# Buttonboard.net
KiCad netlist of a schematic drawn in Altium Designer
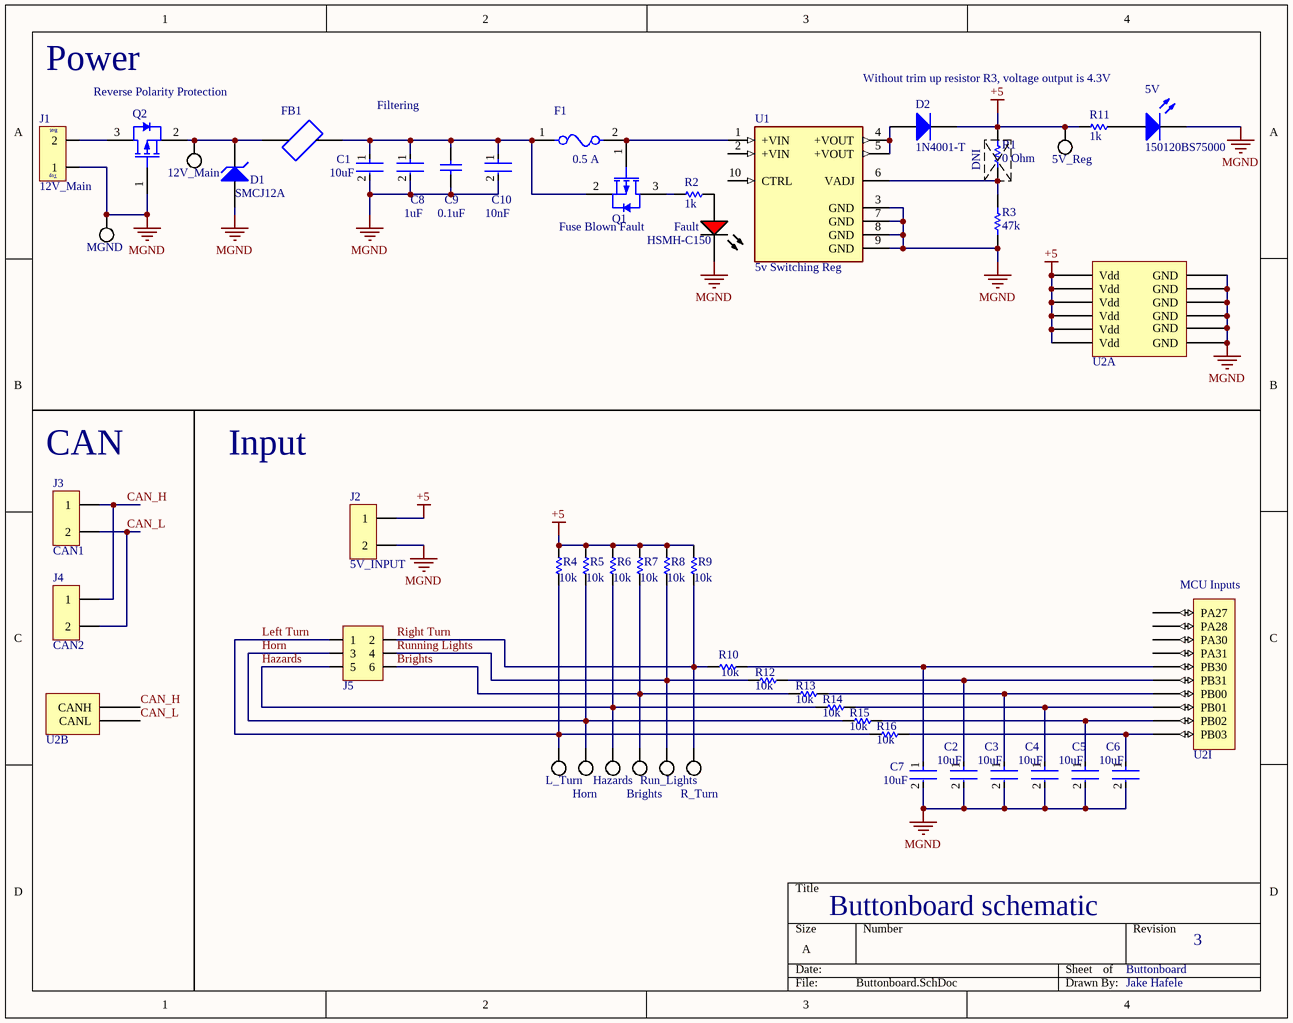
[diagram p0: Buttonboard.SchDoc]

(export (version "E")
  (design (tool "Eeschema 10.0.6"))
  (components
    (comp (ref "5V")
      (value "150120BS75000")
      (footprint "1206_A")
      (description "SMD mono-color Chip LED, WL-SMCW, Blue")
      (fields (field (name "MANUFACTURER") "Wuerth Elektronik"))
      (libsource (lib "Altium Content Vault") (part "WE-LED_K1A2-2"))
    )
    (comp (ref "5V_Reg")
      (value "EPAD")
      (footprint "EPAD")
      (description "Pad for probing signals")
      (libsource (lib "PrISUm-Discrete") (part "EPAD"))
    )
    (comp (ref "12V_Main")
      (value "EPAD")
      (footprint "EPAD")
      (description "Pad for probing signals")
      (libsource (lib "PrISUm-Discrete") (part "EPAD"))
    )
    (comp (ref "Brights")
      (value "EPAD")
      (footprint "EPAD")
      (description "Pad for probing signals")
      (libsource (lib "PrISUm-Discrete") (part "EPAD"))
    )
    (comp (ref "C1")
      (value "CL31A106MOHNNNE")
      (footprint "FP-CL31-IPC_A")
      (description "Cap Ceramic 10uF 16V X5R ±20% SMD 1206 +85°C Embossed T/R")
      (fields (field (name "CAPACITANCE") "10uF") (field (name "TOLERANCE") "20%"))
      (libsource (lib "Altium Content Vault") (part "b4654b650e69147ec39a6b967a45e02"))
    )
    (comp (ref "C2")
      (value "CL31A106MOHNNNE")
      (footprint "FP-CL31-IPC_A")
      (description "Cap Ceramic 10uF 16V X5R ±20% SMD 1206 +85°C Embossed T/R")
      (fields (field (name "CAPACITANCE") "10uF") (field (name "TOLERANCE") "20%"))
      (libsource (lib "Altium Content Vault") (part "b4654b650e69147ec39a6b967a45e02"))
    )
    (comp (ref "C3")
      (value "CL31A106MOHNNNE")
      (footprint "FP-CL31-IPC_A")
      (description "Cap Ceramic 10uF 16V X5R ±20% SMD 1206 +85°C Embossed T/R")
      (fields (field (name "CAPACITANCE") "10uF") (field (name "TOLERANCE") "20%"))
      (libsource (lib "Altium Content Vault") (part "b4654b650e69147ec39a6b967a45e02"))
    )
    (comp (ref "C4")
      (value "CL31A106MOHNNNE")
      (footprint "FP-CL31-IPC_A")
      (description "Cap Ceramic 10uF 16V X5R ±20% SMD 1206 +85°C Embossed T/R")
      (fields (field (name "CAPACITANCE") "10uF") (field (name "TOLERANCE") "20%"))
      (libsource (lib "Altium Content Vault") (part "b4654b650e69147ec39a6b967a45e02"))
    )
    (comp (ref "C5")
      (value "CL31A106MOHNNNE")
      (footprint "FP-CL31-IPC_A")
      (description "Cap Ceramic 10uF 16V X5R ±20% SMD 1206 +85°C Embossed T/R")
      (fields (field (name "CAPACITANCE") "10uF") (field (name "TOLERANCE") "20%"))
      (libsource (lib "Altium Content Vault") (part "b4654b650e69147ec39a6b967a45e02"))
    )
    (comp (ref "C6")
      (value "CL31A106MOHNNNE")
      (footprint "FP-CL31-IPC_A")
      (description "Cap Ceramic 10uF 16V X5R ±20% SMD 1206 +85°C Embossed T/R")
      (fields (field (name "CAPACITANCE") "10uF") (field (name "TOLERANCE") "20%"))
      (libsource (lib "Altium Content Vault") (part "b4654b650e69147ec39a6b967a45e02"))
    )
    (comp (ref "C7")
      (value "CL31A106MOHNNNE")
      (footprint "FP-CL31-IPC_A")
      (description "Cap Ceramic 10uF 16V X5R ±20% SMD 1206 +85°C Embossed T/R")
      (fields (field (name "CAPACITANCE") "10uF") (field (name "TOLERANCE") "20%"))
      (libsource (lib "Altium Content Vault") (part "b4654b650e69147ec39a6b967a45e02"))
    )
    (comp (ref "C8")
      (value "CL31F105ZOCNNNC")
      (footprint "FP-CL31-IPC_A")
      (description "Cap Ceramic 1uF 16V Y5V -20/+80% SMD 1206 +85°C Embossed T/R")
      (fields (field (name "TOLERANCE") "80%") (field (name "CAPACITANCE") "1uF"))
      (libsource (lib "Altium Content Vault") (part "b4654b650e69147ec39a6b967a45e02"))
    )
    (comp (ref "C9")
      (value "08055C104JAT2A")
      (footprint "CAPC2013X94X50LL20T25")
      (description "Chip Capacitor, 0.1 uF, +/- 5%, 50 V, -55 to 125 degC, 0805 (2012 Metric), RoHS, Tape and Reel")
      (fields
        (field (name "CAPACITANCE") "0.1uF")
        (field (name "TOLERANCE") "5%")
        (field (name "MANUFACTURER") "AVX")
      )
      (libsource (lib "Altium Content Vault") (part "CAP-NP-2"))
    )
    (comp (ref "C10")
      (value "CGA3E2X8R2A103K080AD")
      (footprint "FP-CGA3E-0_3-0_1-IPC_A")
      (description "Cap Ceramic 10nF 100V X8R 10% Pad SMD 0603 +150°C Automotive T/R")
      (fields (field (name "CAPACITANCE") "10nF") (field (name "TOLERANCE") "10%"))
      (libsource (lib "Altium Content Vault") (part "b4654b650e69147ec39a6b967a45e02"))
    )
    (comp (ref "D1")
      (value "SMCJ12A")
      (footprint "LFUS-DO-214AB-2_V")
      (fields (field (name "MANUFACTURER") "Littelfuse"))
      (libsource (lib "Altium Content Vault") (part "DZEN-AK-2"))
    )
    (comp (ref "D2")
      (value "1N4001-T")
      (footprint "DIOD-DO-41-P-2_V")
      (description "1.0 A Rectifier, 15 pF, 50 V, -65 to 150 degC, 2-Pin DO-41 Plastic, RoHS, Tape and Reel")
      (fields (field (name "MANUFACTURER") "Diodes Inc"))
      (libsource (lib "Altium Content Vault") (part "DIOD-D-A1K2-2"))
    )
    (comp (ref "DNI") (value "DO NOT INSTALL") (libsource (lib "PrISUm-Discrete") (part "DNI")))
    (comp (ref "F1")
      (value "0.5 A")
      (footprint "FP-0155-MFG")
      (description "FUSE BLOK CARTRIDGE 125V 10A SMD")
      (fields
        (field (name "MANUFACTURER") "Littelfuse Inc")
        (field (name "OCTOPART") "https://octopart.com/01550900m-littelfuse-9291575")
      )
      (libsource (lib "Altium Content Vault") (part "5bcf9b9f640e542cf0359d10258e979"))
    )
    (comp (ref "Fault")
      (value "HSMH-C150")
      (footprint "AVAG-HSMX-C150_V")
      (description "LED Uni-Color Red, 65 mW, 25 mA, -40 to 85 degC, 2-Pin SMD, RoHS, Tape and Reel")
      (fields (field (name "MANUFACTURER") "Avago"))
      (libsource (lib "Altium Content Vault") (part "LED-RED-AK-2"))
    )
    (comp (ref "FB1")
      (value "HI1206N800R-10")
      (footprint "FB_HI1206N800R-10")
      (description "80 Ohms @ 100MHz 1 Power, Signal Line Ferrite Bead 1206 (3216 Metric) 3A 35mOhm")
      (fields
        (field (name "MF") "Laird-Signal Integrity")
        (field (name "DIGI-KEY_PART_NUMBER") "240-2409-1-ND")
      )
      (libsource (lib "HI1206N800R-10") (part "HI1206N800R-10"))
    )
    (comp (ref "Hazards")
      (value "EPAD")
      (footprint "EPAD")
      (description "Pad for probing signals")
      (libsource (lib "PrISUm-Discrete") (part "EPAD"))
    )
    (comp (ref "Horn")
      (value "EPAD")
      (footprint "EPAD")
      (description "Pad for probing signals")
      (libsource (lib "PrISUm-Discrete") (part "EPAD"))
    )
    (comp (ref "J1")
      (value "12V_Main")
      (footprint "CONN_2P_MEGAFIT_HORIZONTAL")
      (fields
        (field (name "MANUFACTURER PART NUMBER") "0768250002")
        (field (name "MANUFACTURER") "Molex")
        (field (name "DIGIKEY PART NUMBER") "WM11969-ND")
      )
      (libsource (lib "Connectors") (part "CONN_2P_MEGAFIT_HORIZONTAL"))
    )
    (comp (ref "J2")
      (value "5V_INPUT")
      (footprint "Mini-Fit Jr. 2")
      (description "Mini-Fit Jr. 2-pin Right Angle")
      (fields
        (field (name "MANUFACTURER") "Molex Inc")
        (field (name "MANUFACTURER PART NUMBER") "0039300020")
      )
      (libsource (lib "PrISUm-Connectors") (part "Mini-Fit Jr. 2-pin"))
    )
    (comp (ref "J3")
      (value "CAN1")
      (footprint "Mini-Fit Jr. 2")
      (description "Mini-Fit Jr. 2-pin Right Angle")
      (fields
        (field (name "MANUFACTURER") "Molex Inc")
        (field (name "MANUFACTURER PART NUMBER") "0039300020")
      )
      (libsource (lib "PrISUm-Connectors") (part "Mini-Fit Jr. 2-pin"))
    )
    (comp (ref "J4")
      (value "CAN2")
      (footprint "Mini-Fit Jr. 2")
      (description "Mini-Fit Jr. 2-pin Right Angle")
      (fields
        (field (name "MANUFACTURER") "Molex Inc")
        (field (name "MANUFACTURER PART NUMBER") "0039300020")
      )
      (libsource (lib "PrISUm-Connectors") (part "Mini-Fit Jr. 2-pin"))
    )
    (comp (ref "J5")
      (value "Molex Mini-Fit Jr. 6-Pin")
      (footprint "Molex Mini-Fit Jr. 6-Pin")
      (description "6-Pin Molex Mini-Fit Jr. Header  through hole")
      (fields (field (name "MANUFACTURER") "Molex") (field (name "DRAWN BY") "Aaron Mills"))
      (libsource (lib "PrISUm-Connectors") (part "Molex Mini-Fit Jr. 6-Pin"))
    )
    (comp (ref "L_Turn")
      (value "EPAD")
      (footprint "EPAD")
      (description "Pad for probing signals")
      (libsource (lib "PrISUm-Discrete") (part "EPAD"))
    )
    (comp (ref "MGND")
      (value "EPAD")
      (footprint "EPAD")
      (description "Pad for probing signals")
      (libsource (lib "PrISUm-Discrete") (part "EPAD"))
    )
    (comp (ref "Q1")
      (value "Fuse Blown Fault")
      (footprint "INTR-SOT-23-3_V")
      (fields (field (name "MANUFACTURER") "International Rectifier"))
      (libsource (lib "Altium Content Vault") (part "PEMOS-GSD-3"))
    )
    (comp (ref "Q2")
      (value "Reverse Polarity Protection")
      (footprint "INTR-SOT-23-3_V")
      (fields (field (name "MANUFACTURER") "International Rectifier"))
      (libsource (lib "Altium Content Vault") (part "PEMOS-GSD-3"))
    )
    (comp (ref "R1")
      (value "0 Ohm")
      (footprint "RESC2013X50X30LL20T20")
      (fields (field (name "PART NUMBER") "CRCW080533K0JNEA") (field (name "MANUFACTURER") "Vishay Dale"))
      (libsource (lib "Altium Content Vault") (part "RES"))
    )
    (comp (ref "R2")
      (value "1k")
      (footprint "0805_B")
      (fields (field (name "Comment") "Resistor"))
      (libsource (lib "Resistors") (part "Resistor"))
    )
    (comp (ref "R3")
      (value "47k")
      (footprint "RESC2013X60X35ML10T20")
      (fields (field (name "MANUFACTURER") "Yageo") (field (name "PART NUMBER") "RC0805FR-078K66L"))
      (libsource (lib "Altium Content Vault") (part "RES"))
    )
    (comp (ref "R4")
      (value "10k")
      (footprint "0805_B")
      (description "0805 10kOhm resistor 1% 1/8W")
      (fields (field (name "Comment") "1% 1/8W"))
      (libsource (lib "Resistors") (part "MCR10EZHF1002"))
    )
    (comp (ref "R5")
      (value "10k")
      (footprint "0805_B")
      (description "0805 10kOhm resistor 1% 1/8W")
      (fields (field (name "Comment") "1% 1/8W"))
      (libsource (lib "Resistors") (part "MCR10EZHF1002"))
    )
    (comp (ref "R6")
      (value "10k")
      (footprint "0805_B")
      (description "0805 10kOhm resistor 1% 1/8W")
      (fields (field (name "Comment") "1% 1/8W"))
      (libsource (lib "Resistors") (part "MCR10EZHF1002"))
    )
    (comp (ref "R7")
      (value "10k")
      (footprint "0805_B")
      (description "0805 10kOhm resistor 1% 1/8W")
      (fields (field (name "Comment") "1% 1/8W"))
      (libsource (lib "Resistors") (part "MCR10EZHF1002"))
    )
    (comp (ref "R8")
      (value "10k")
      (footprint "0805_B")
      (description "0805 10kOhm resistor 1% 1/8W")
      (fields (field (name "Comment") "1% 1/8W"))
      (libsource (lib "Resistors") (part "MCR10EZHF1002"))
    )
    (comp (ref "R9")
      (value "10k")
      (footprint "0805_B")
      (description "0805 10kOhm resistor 1% 1/8W")
      (fields (field (name "Comment") "1% 1/8W"))
      (libsource (lib "Resistors") (part "MCR10EZHF1002"))
    )
    (comp (ref "R10")
      (value "10k")
      (footprint "0805_B")
      (description "0805 10kOhm resistor 1% 1/8W")
      (fields (field (name "Comment") "1% 1/8W"))
      (libsource (lib "Resistors") (part "MCR10EZHF1002"))
    )
    (comp (ref "R11")
      (value "1k")
      (footprint "0805_B")
      (fields (field (name "Comment") "Resistor"))
      (libsource (lib "Resistors") (part "Resistor"))
    )
    (comp (ref "R12")
      (value "10k")
      (footprint "0805_B")
      (description "0805 10kOhm resistor 1% 1/8W")
      (fields (field (name "Comment") "1% 1/8W"))
      (libsource (lib "Resistors") (part "MCR10EZHF1002"))
    )
    (comp (ref "R13")
      (value "10k")
      (footprint "0805_B")
      (description "0805 10kOhm resistor 1% 1/8W")
      (fields (field (name "Comment") "1% 1/8W"))
      (libsource (lib "Resistors") (part "MCR10EZHF1002"))
    )
    (comp (ref "R14")
      (value "10k")
      (footprint "0805_B")
      (description "0805 10kOhm resistor 1% 1/8W")
      (fields (field (name "Comment") "1% 1/8W"))
      (libsource (lib "Resistors") (part "MCR10EZHF1002"))
    )
    (comp (ref "R15")
      (value "10k")
      (footprint "0805_B")
      (description "0805 10kOhm resistor 1% 1/8W")
      (fields (field (name "Comment") "1% 1/8W"))
      (libsource (lib "Resistors") (part "MCR10EZHF1002"))
    )
    (comp (ref "R16")
      (value "10k")
      (footprint "0805_B")
      (description "0805 10kOhm resistor 1% 1/8W")
      (fields (field (name "Comment") "1% 1/8W"))
      (libsource (lib "Resistors") (part "MCR10EZHF1002"))
    )
    (comp (ref "Run_Lights")
      (value "EPAD")
      (footprint "EPAD")
      (description "Pad for probing signals")
      (libsource (lib "PrISUm-Discrete") (part "EPAD"))
    )
    (comp (ref "R_Turn")
      (value "EPAD")
      (footprint "EPAD")
      (description "Pad for probing signals")
      (libsource (lib "PrISUm-Discrete") (part "EPAD"))
    )
    (comp (ref "U1")
      (value "5v Switching Reg")
      (footprint "5v Reg")
      (description "1A DC/DC-Converter 'INNOLINE' SMD reg")
      (fields (field (name "MF") "Recom Power") (field (name "MP") "R-78AA5.0-1.0SMD-R"))
      (libsource (lib "PrISUm-ICs") (part "5v Switching Reg"))
    )
    (comp (ref "U2")
      (value "S+")
      (footprint "Compute S+")
      (description "Need to get 4 of PPPC161LFBN-RC")
      (libsource (lib "PrISUm-ICs") (part "S+"))
    )
  )
  (nets
    (net (code "1") (name "+5") (class "Default")
      (node (ref "5V_Reg") (pin "1") (pinfunction "1_1") (pintype "passive"))
      (node (ref "D2") (pin "2") (pinfunction "K_2") (pintype "passive"))
      (node (ref "J2") (pin "1") (pinfunction "1_1") (pintype "passive"))
      (node (ref "R1") (pin "2") (pinfunction "2_2") (pintype "passive"))
      (node (ref "R11") (pin "2") (pinfunction "2_2") (pintype "passive"))
      (node (ref "R4") (pin "2") (pinfunction "2_2") (pintype "passive"))
      (node (ref "R5") (pin "2") (pinfunction "2_2") (pintype "passive"))
      (node (ref "R6") (pin "2") (pinfunction "2_2") (pintype "passive"))
      (node (ref "R7") (pin "2") (pinfunction "2_2") (pintype "passive"))
      (node (ref "R8") (pin "2") (pinfunction "2_2") (pintype "passive"))
      (node (ref "R9") (pin "2") (pinfunction "2_2") (pintype "passive"))
      (node (ref "U2") (pin "Vdd") (pinfunction "Vdd_Vdd") (pintype "passive"))
    )
    (net (code "2") (name "/Brights") (class "Default")
      (node (ref "Brights") (pin "1") (pinfunction "1_1") (pintype "passive"))
      (node (ref "J5") (pin "6") (pinfunction "6_6") (pintype "passive"))
      (node (ref "R13") (pin "2") (pinfunction "2_2") (pintype "passive"))
      (node (ref "R7") (pin "1") (pinfunction "1_1") (pintype "passive"))
    )
    (net (code "3") (name "/CAN_H") (class "Default")
      (node (ref "J3") (pin "1") (pinfunction "1_1") (pintype "passive"))
      (node (ref "J4") (pin "1") (pinfunction "1_1") (pintype "passive"))
      (node (ref "U2") (pin "CANH") (pinfunction "CANH_CANH") (pintype "passive"))
    )
    (net (code "4") (name "/CAN_L") (class "Default")
      (node (ref "J3") (pin "2") (pinfunction "2_2") (pintype "passive"))
      (node (ref "J4") (pin "2") (pinfunction "2_2") (pintype "passive"))
      (node (ref "U2") (pin "CANL") (pinfunction "CANL_CANL") (pintype "passive"))
    )
    (net (code "5") (name "/Hazards") (class "Default")
      (node (ref "Hazards") (pin "1") (pinfunction "1_1") (pintype "passive"))
      (node (ref "J5") (pin "5") (pinfunction "5_5") (pintype "passive"))
      (node (ref "R14") (pin "2") (pinfunction "2_2") (pintype "passive"))
      (node (ref "R6") (pin "1") (pinfunction "1_1") (pintype "passive"))
    )
    (net (code "6") (name "/Horn") (class "Default")
      (node (ref "Horn") (pin "1") (pinfunction "1_1") (pintype "passive"))
      (node (ref "J5") (pin "3") (pinfunction "3_3") (pintype "passive"))
      (node (ref "R15") (pin "2") (pinfunction "2_2") (pintype "passive"))
      (node (ref "R5") (pin "1") (pinfunction "1_1") (pintype "passive"))
    )
    (net (code "7") (name "/Left Turn") (class "Default")
      (node (ref "J5") (pin "1") (pinfunction "1_1") (pintype "passive"))
      (node (ref "L_Turn") (pin "1") (pinfunction "1_1") (pintype "passive"))
      (node (ref "R16") (pin "2") (pinfunction "2_2") (pintype "passive"))
      (node (ref "R4") (pin "1") (pinfunction "1_1") (pintype "passive"))
    )
    (net (code "8") (name "/Right Turn") (class "Default")
      (node (ref "J5") (pin "2") (pinfunction "2_2") (pintype "passive"))
      (node (ref "R10") (pin "2") (pinfunction "2_2") (pintype "passive"))
      (node (ref "R9") (pin "1") (pinfunction "1_1") (pintype "passive"))
      (node (ref "R_Turn") (pin "1") (pinfunction "1_1") (pintype "passive"))
    )
    (net (code "9") (name "/Running Lights") (class "Default")
      (node (ref "J5") (pin "4") (pinfunction "4_4") (pintype "passive"))
      (node (ref "R12") (pin "2") (pinfunction "2_2") (pintype "passive"))
      (node (ref "R8") (pin "1") (pinfunction "1_1") (pintype "passive"))
      (node (ref "Run_Lights") (pin "1") (pinfunction "1_1") (pintype "passive"))
    )
    (net (code "10") (name "MGND") (class "Default")
      (node (ref "5V") (pin "1") (pinfunction "K_1") (pintype "passive"))
      (node (ref "C1") (pin "2") (pinfunction "2_2") (pintype "passive"))
      (node (ref "C10") (pin "2") (pinfunction "2_2") (pintype "passive"))
      (node (ref "C2") (pin "2") (pinfunction "2_2") (pintype "passive"))
      (node (ref "C3") (pin "2") (pinfunction "2_2") (pintype "passive"))
      (node (ref "C4") (pin "2") (pinfunction "2_2") (pintype "passive"))
      (node (ref "C5") (pin "2") (pinfunction "2_2") (pintype "passive"))
      (node (ref "C6") (pin "2") (pinfunction "2_2") (pintype "passive"))
      (node (ref "C7") (pin "2") (pinfunction "2_2") (pintype "passive"))
      (node (ref "C8") (pin "2") (pinfunction "2_2") (pintype "passive"))
      (node (ref "C9") (pin "1") (pinfunction "1_1") (pintype "passive"))
      (node (ref "D1") (pin "1") (pinfunction "A_1") (pintype "passive"))
      (node (ref "Fault") (pin "2") (pinfunction "K_2") (pintype "passive"))
      (node (ref "J1") (pin "1") (pinfunction "1_1") (pintype "passive"))
      (node (ref "J2") (pin "2") (pinfunction "2_2") (pintype "passive"))
      (node (ref "MGND") (pin "1") (pinfunction "1_1") (pintype "passive"))
      (node (ref "Q2") (pin "1") (pinfunction "GATE_1") (pintype "passive"))
      (node (ref "R3") (pin "1") (pinfunction "1_1") (pintype "passive"))
      (node (ref "U1") (pin "3") (pinfunction "GND_3") (pintype "power_in"))
      (node (ref "U1") (pin "7") (pinfunction "GND_7") (pintype "power_in"))
      (node (ref "U1") (pin "8") (pinfunction "GND_8") (pintype "power_in"))
      (node (ref "U1") (pin "9") (pinfunction "GND_9") (pintype "power_in"))
      (node (ref "U2") (pin "GND") (pinfunction "GND_GND") (pintype "passive"))
    )
    (net (code "11") (name "Net-(5V-A)") (class "Default")
      (node (ref "5V") (pin "2") (pinfunction "A_2") (pintype "passive"))
      (node (ref "R11") (pin "1") (pinfunction "1_1") (pintype "passive"))
    )
    (net (code "12") (name "Net-(C2-Pad1)") (class "Default")
      (node (ref "C2") (pin "1") (pinfunction "1_1") (pintype "passive"))
      (node (ref "R12") (pin "1") (pinfunction "1_1") (pintype "passive"))
      (node (ref "U2") (pin "PB31") (pinfunction "PB31_PB31") (pintype "bidirectional"))
    )
    (net (code "13") (name "Net-(C3-Pad1)") (class "Default")
      (node (ref "C3") (pin "1") (pinfunction "1_1") (pintype "passive"))
      (node (ref "R13") (pin "1") (pinfunction "1_1") (pintype "passive"))
      (node (ref "U2") (pin "PB00") (pinfunction "PB00_PB00") (pintype "bidirectional"))
    )
    (net (code "14") (name "Net-(C4-Pad1)") (class "Default")
      (node (ref "C4") (pin "1") (pinfunction "1_1") (pintype "passive"))
      (node (ref "R14") (pin "1") (pinfunction "1_1") (pintype "passive"))
      (node (ref "U2") (pin "PB01") (pinfunction "PB01_PB01") (pintype "bidirectional"))
    )
    (net (code "15") (name "Net-(C5-Pad1)") (class "Default")
      (node (ref "C5") (pin "1") (pinfunction "1_1") (pintype "passive"))
      (node (ref "R15") (pin "1") (pinfunction "1_1") (pintype "passive"))
      (node (ref "U2") (pin "PB02") (pinfunction "PB02_PB02") (pintype "bidirectional"))
    )
    (net (code "16") (name "Net-(C6-Pad1)") (class "Default")
      (node (ref "C6") (pin "1") (pinfunction "1_1") (pintype "passive"))
      (node (ref "R16") (pin "1") (pinfunction "1_1") (pintype "passive"))
      (node (ref "U2") (pin "PB03") (pinfunction "PB03_PB03") (pintype "bidirectional"))
    )
    (net (code "17") (name "Net-(C7-Pad1)") (class "Default")
      (node (ref "C7") (pin "1") (pinfunction "1_1") (pintype "passive"))
      (node (ref "R10") (pin "1") (pinfunction "1_1") (pintype "passive"))
      (node (ref "U2") (pin "PB30") (pinfunction "PB30_PB30") (pintype "bidirectional"))
    )
    (net (code "18") (name "Net-(D1-K)") (class "Default")
      (node (ref "12V_Main") (pin "1") (pinfunction "1_1") (pintype "passive"))
      (node (ref "D1") (pin "2") (pinfunction "K_2") (pintype "passive"))
      (node (ref "FB1") (pin "1") (pinfunction "1_1") (pintype "passive"))
      (node (ref "Q2") (pin "2") (pinfunction "SOURCE_2") (pintype "passive"))
    )
    (net (code "19") (name "Net-(D2-A)") (class "Default")
      (node (ref "D2") (pin "1") (pinfunction "A_1") (pintype "passive"))
      (node (ref "U1") (pin "4") (pinfunction "+VOUT_4") (pintype "output"))
      (node (ref "U1") (pin "5") (pinfunction "+VOUT_5") (pintype "output"))
    )
    (net (code "20") (name "Net-(Fault-A)") (class "Default")
      (node (ref "Fault") (pin "1") (pinfunction "A_1") (pintype "passive"))
      (node (ref "R2") (pin "2") (pinfunction "2_2") (pintype "passive"))
    )
    (net (code "21") (name "Net-(Q1-DRAIN)") (class "Default")
      (node (ref "Q1") (pin "3") (pinfunction "DRAIN_3") (pintype "passive"))
      (node (ref "R2") (pin "1") (pinfunction "1_1") (pintype "passive"))
    )
    (net (code "22") (name "Net-(Q1-GATE)") (class "Default")
      (node (ref "F1") (pin "2") (pinfunction "2_2") (pintype "passive"))
      (node (ref "Q1") (pin "1") (pinfunction "GATE_1") (pintype "passive"))
      (node (ref "U1") (pin "1") (pinfunction "+VIN_1") (pintype "input"))
    )
    (net (code "23") (name "Net-(Q1-SOURCE)") (class "Default")
      (node (ref "C1") (pin "1") (pinfunction "1_1") (pintype "passive"))
      (node (ref "C10") (pin "1") (pinfunction "1_1") (pintype "passive"))
      (node (ref "C8") (pin "1") (pinfunction "1_1") (pintype "passive"))
      (node (ref "C9") (pin "2") (pinfunction "2_2") (pintype "passive"))
      (node (ref "F1") (pin "1") (pinfunction "1_1") (pintype "passive"))
      (node (ref "FB1") (pin "2") (pinfunction "2_2") (pintype "passive"))
      (node (ref "Q1") (pin "2") (pinfunction "SOURCE_2") (pintype "passive"))
    )
    (net (code "24") (name "Net-(Q2-DRAIN)") (class "Default")
      (node (ref "J1") (pin "2") (pinfunction "2_2") (pintype "passive"))
      (node (ref "Q2") (pin "3") (pinfunction "DRAIN_3") (pintype "passive"))
    )
    (net (code "25") (name "Net-(U1-VADJ)") (class "Default")
      (node (ref "R1") (pin "1") (pinfunction "1_1") (pintype "passive"))
      (node (ref "R3") (pin "2") (pinfunction "2_2") (pintype "passive"))
      (node (ref "U1") (pin "6") (pinfunction "VADJ_6") (pintype "passive"))
    )
    (net (code "26") (name "unconnected-(U1-+VIN-Pad2)") (class "Default")
      (node (ref "U1") (pin "2") (pinfunction "+VIN_2") (pintype "input"))
    )
    (net (code "27") (name "unconnected-(U1-CTRL-Pad10)") (class "Default")
      (node (ref "U1") (pin "10") (pinfunction "CTRL_10") (pintype "input"))
    )
    (net (code "28") (name "unconnected-(U2-PadPA27)") (class "Default")
      (node (ref "U2") (pin "PA27") (pinfunction "PA27_PA27") (pintype "bidirectional"))
    )
    (net (code "29") (name "unconnected-(U2-PadPA28)") (class "Default")
      (node (ref "U2") (pin "PA28") (pinfunction "PA28_PA28") (pintype "bidirectional"))
    )
    (net (code "30") (name "unconnected-(U2-PadPA30)") (class "Default")
      (node (ref "U2") (pin "PA30") (pinfunction "PA30_PA30") (pintype "bidirectional"))
    )
    (net (code "31") (name "unconnected-(U2-PadPA31)") (class "Default")
      (node (ref "U2") (pin "PA31") (pinfunction "PA31_PA31") (pintype "bidirectional"))
    )
  )
)
